# 13_Clocks_1.net
KiCad netlist of a schematic drawn in Altium Designer
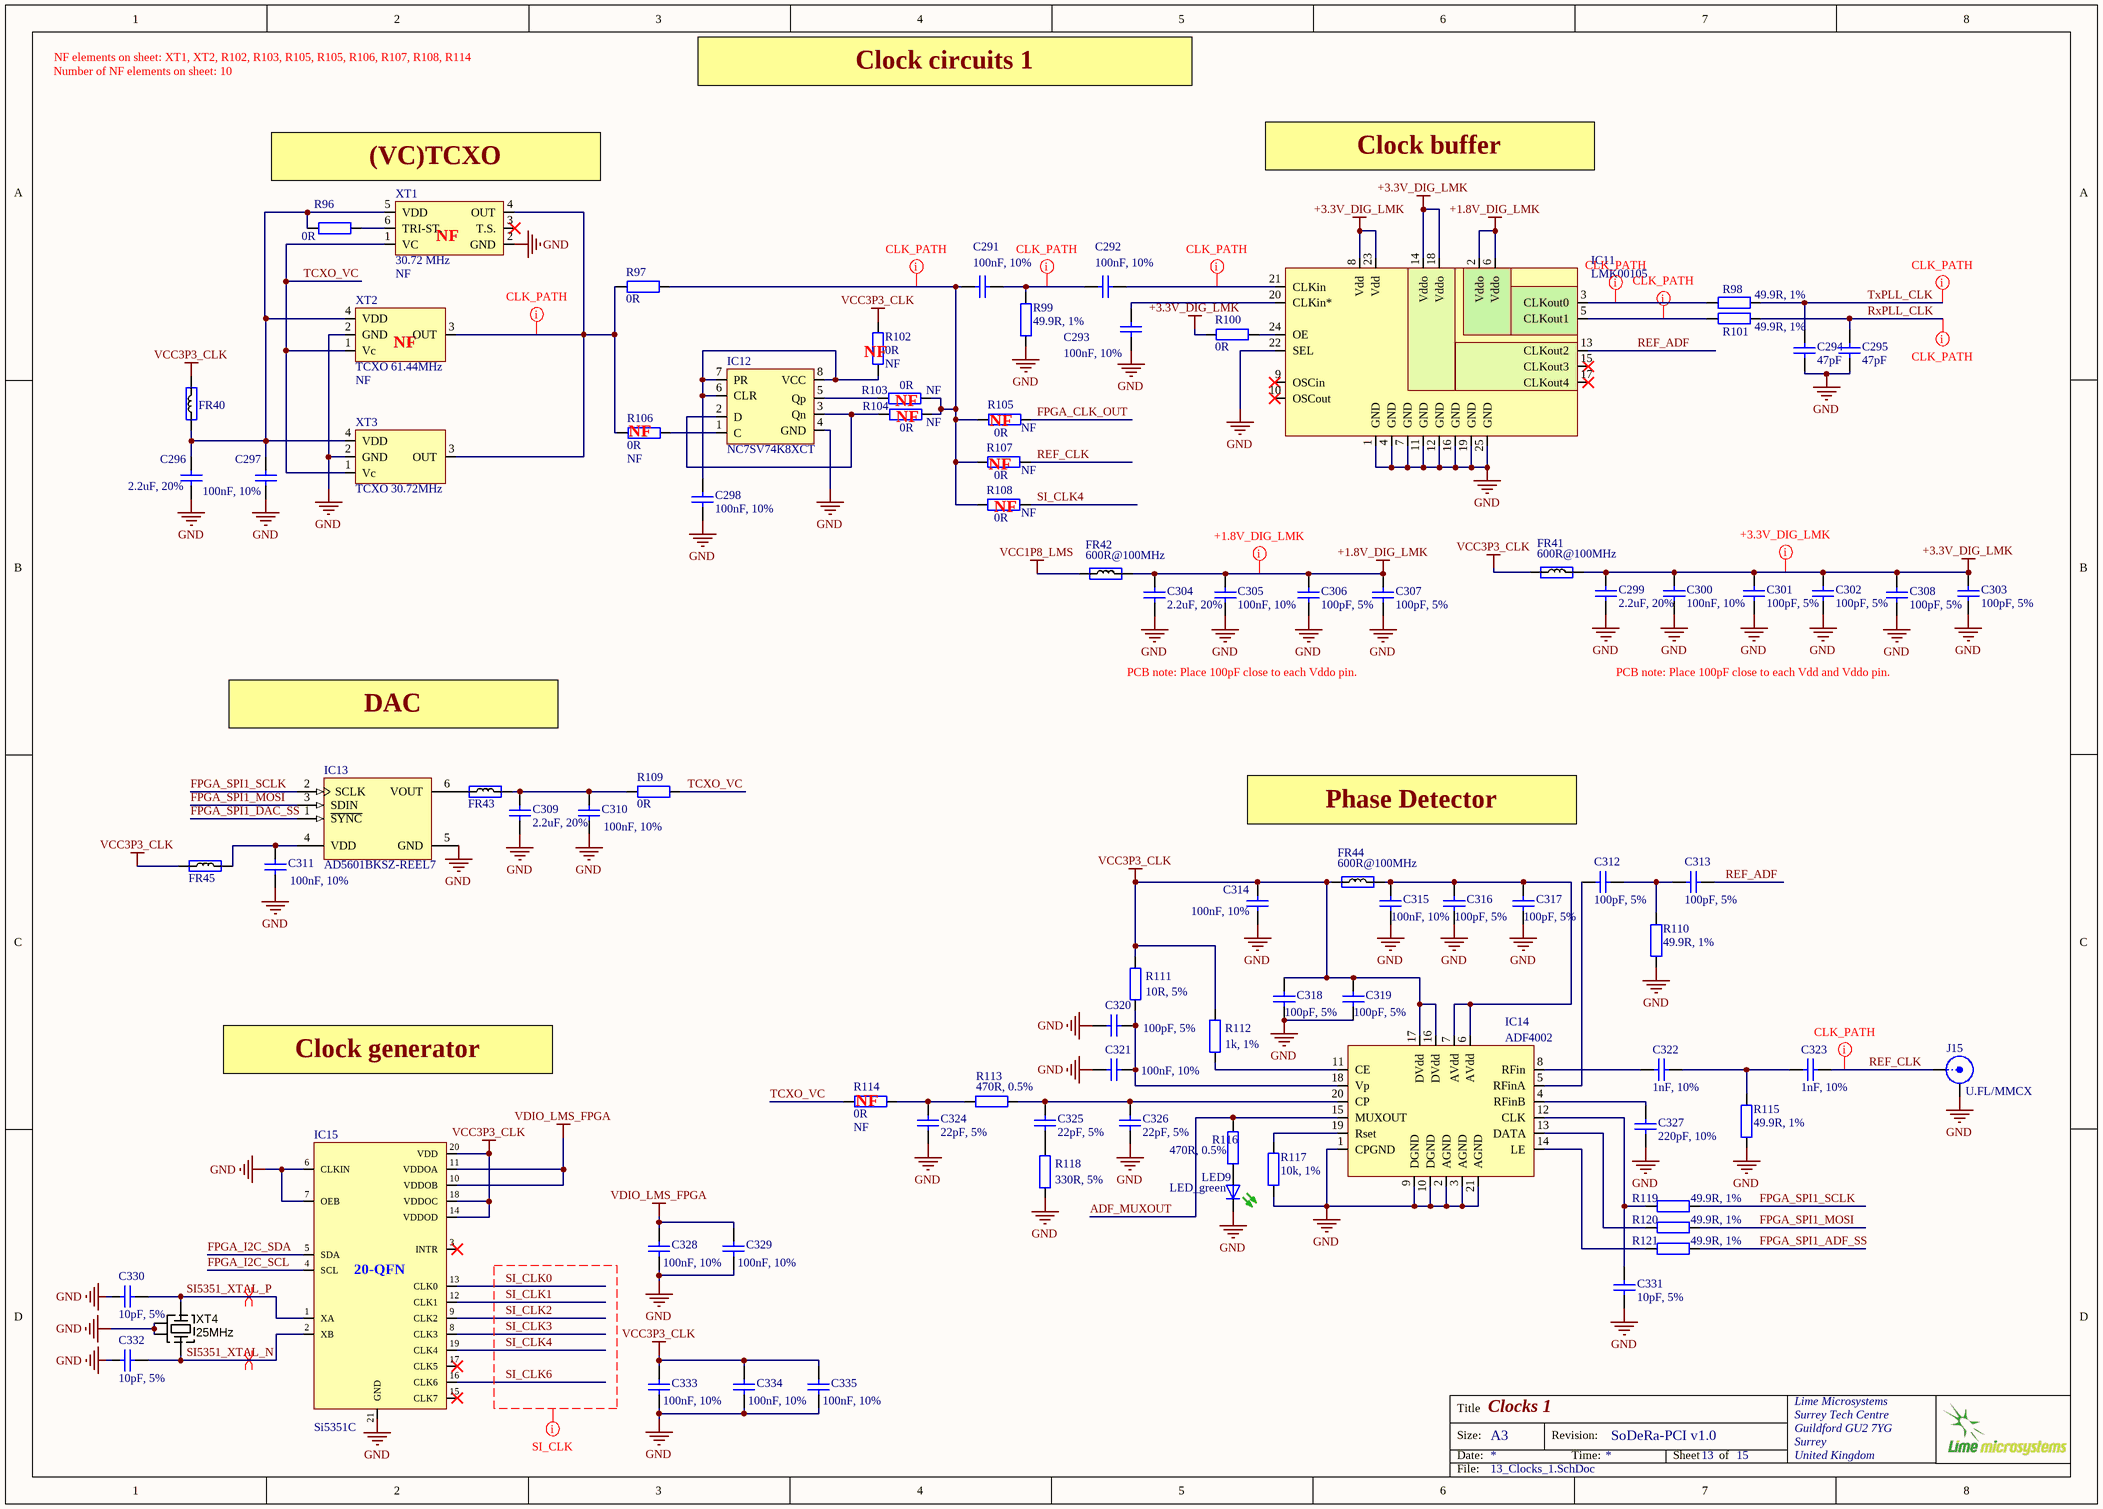
[diagram p0: 13_Clocks_1.SchDoc]

(export (version "E")
  (design (tool "Eeschema 10.0.6"))
  (components
    (comp (ref "C291")
      (value "100nF, 10%")
      (footprint "LimeMicroAltiumLib_pcbLib:CAP0402")
      (fields
        (field (name "MANUFACTURER") "Murata Electronics")
        (field (name "TOLERANCE") "10 %")
        (field (name "MANUFACTURER PART NUMBER") "GRM155R71C104KA88D")
      )
      (libsource (lib "LimeMicroAltiumLib_schLib") (part "Cap_0402"))
    )
    (comp (ref "C292")
      (value "100nF, 10%")
      (footprint "LimeMicroAltiumLib_pcbLib:CAP0402")
      (fields
        (field (name "MANUFACTURER") "Murata Electronics")
        (field (name "TOLERANCE") "10 %")
        (field (name "MANUFACTURER PART NUMBER") "GRM155R71C104KA88D")
      )
      (libsource (lib "LimeMicroAltiumLib_schLib") (part "Cap_0402"))
    )
    (comp (ref "C293")
      (value "100nF, 10%")
      (footprint "LimeMicroAltiumLib_pcbLib:CAP0402")
      (fields
        (field (name "MANUFACTURER") "Murata Electronics")
        (field (name "TOLERANCE") "10 %")
        (field (name "MANUFACTURER PART NUMBER") "GRM155R71C104KA88D")
      )
      (libsource (lib "LimeMicroAltiumLib_schLib") (part "Cap_0402"))
    )
    (comp (ref "C294")
      (value "47pF")
      (footprint "LimeMicroAltiumLib_pcbLib:CAP0402")
      (fields (field (name "TOLERANCE") "±1%") (field (name "MANUFACTURER") "TDK Corporation"))
      (libsource (lib "LimeMicroAltiumLib_schLib") (part "Cap_0402"))
    )
    (comp (ref "C295")
      (value "47pF")
      (footprint "LimeMicroAltiumLib_pcbLib:CAP0402")
      (fields (field (name "TOLERANCE") "±1%") (field (name "MANUFACTURER") "TDK Corporation"))
      (libsource (lib "LimeMicroAltiumLib_schLib") (part "Cap_0402"))
    )
    (comp (ref "C296")
      (value "2.2uF, 20%")
      (footprint "LimeMicroAltiumLib_pcbLib:CAP0402")
      (fields (field (name "MANUFACTURER") "TDK Corporation") (field (name "TOLERANCE") "±20%"))
      (libsource (lib "LimeMicroAltiumLib_schLib") (part "Cap_0402"))
    )
    (comp (ref "C297")
      (value "100nF, 10%")
      (footprint "LimeMicroAltiumLib_pcbLib:CAP0402")
      (fields
        (field (name "MANUFACTURER") "Murata Electronics")
        (field (name "TOLERANCE") "10 %")
        (field (name "MANUFACTURER PART NUMBER") "GRM155R71C104KA88D")
      )
      (libsource (lib "LimeMicroAltiumLib_schLib") (part "Cap_0402"))
    )
    (comp (ref "C298")
      (value "100nF, 10%")
      (footprint "LimeMicroAltiumLib_pcbLib:CAP0402")
      (fields
        (field (name "MANUFACTURER") "Murata Electronics")
        (field (name "TOLERANCE") "10 %")
        (field (name "MANUFACTURER PART NUMBER") "GRM155R71C104KA88D")
      )
      (libsource (lib "LimeMicroAltiumLib_schLib") (part "Cap_0402"))
    )
    (comp (ref "C299")
      (value "2.2uF, 20%")
      (footprint "LimeMicroAltiumLib_pcbLib:CAP0402")
      (fields (field (name "MANUFACTURER") "TDK Corporation") (field (name "TOLERANCE") "±20%"))
      (libsource (lib "LimeMicroAltiumLib_schLib") (part "Cap_0402"))
    )
    (comp (ref "C300")
      (value "100nF, 10%")
      (footprint "LimeMicroAltiumLib_pcbLib:CAP0402")
      (fields
        (field (name "MANUFACTURER") "Murata Electronics")
        (field (name "TOLERANCE") "10 %")
        (field (name "MANUFACTURER PART NUMBER") "GRM155R71C104KA88D")
      )
      (libsource (lib "LimeMicroAltiumLib_schLib") (part "Cap_0402"))
    )
    (comp (ref "C301")
      (value "100pF, 5%")
      (footprint "LimeMicroAltiumLib_pcbLib:CAP0402")
      (fields (field (name "MANUFACTURER") "Yageo") (field (name "TOLERANCE") "±5%"))
      (libsource (lib "LimeMicroAltiumLib_schLib") (part "Cap_0402"))
    )
    (comp (ref "C302")
      (value "100pF, 5%")
      (footprint "LimeMicroAltiumLib_pcbLib:CAP0402")
      (fields (field (name "MANUFACTURER") "Yageo") (field (name "TOLERANCE") "±5%"))
      (libsource (lib "LimeMicroAltiumLib_schLib") (part "Cap_0402"))
    )
    (comp (ref "C303")
      (value "100pF, 5%")
      (footprint "LimeMicroAltiumLib_pcbLib:CAP0402")
      (fields (field (name "MANUFACTURER") "Yageo") (field (name "TOLERANCE") "±5%"))
      (libsource (lib "LimeMicroAltiumLib_schLib") (part "Cap_0402"))
    )
    (comp (ref "C304")
      (value "2.2uF, 20%")
      (footprint "LimeMicroAltiumLib_pcbLib:CAP0402")
      (fields (field (name "MANUFACTURER") "TDK Corporation") (field (name "TOLERANCE") "±20%"))
      (libsource (lib "LimeMicroAltiumLib_schLib") (part "Cap_0402"))
    )
    (comp (ref "C305")
      (value "100nF, 10%")
      (footprint "LimeMicroAltiumLib_pcbLib:CAP0402")
      (fields
        (field (name "MANUFACTURER") "Murata Electronics")
        (field (name "TOLERANCE") "10 %")
        (field (name "MANUFACTURER PART NUMBER") "GRM155R71C104KA88D")
      )
      (libsource (lib "LimeMicroAltiumLib_schLib") (part "Cap_0402"))
    )
    (comp (ref "C306")
      (value "100pF, 5%")
      (footprint "LimeMicroAltiumLib_pcbLib:CAP0402")
      (fields (field (name "MANUFACTURER") "Yageo") (field (name "TOLERANCE") "±5%"))
      (libsource (lib "LimeMicroAltiumLib_schLib") (part "Cap_0402"))
    )
    (comp (ref "C307")
      (value "100pF, 5%")
      (footprint "LimeMicroAltiumLib_pcbLib:CAP0402")
      (fields (field (name "MANUFACTURER") "Yageo") (field (name "TOLERANCE") "±5%"))
      (libsource (lib "LimeMicroAltiumLib_schLib") (part "Cap_0402"))
    )
    (comp (ref "C308")
      (value "100pF, 5%")
      (footprint "LimeMicroAltiumLib_pcbLib:CAP0402")
      (fields (field (name "MANUFACTURER") "Yageo") (field (name "TOLERANCE") "±5%"))
      (libsource (lib "LimeMicroAltiumLib_schLib") (part "Cap_0402"))
    )
    (comp (ref "C309")
      (value "2.2uF, 20%")
      (footprint "LimeMicroAltiumLib_pcbLib:CAP0402")
      (fields (field (name "MANUFACTURER") "TDK Corporation") (field (name "TOLERANCE") "±20%"))
      (libsource (lib "LimeMicroAltiumLib_schLib") (part "Cap_0402"))
    )
    (comp (ref "C310")
      (value "100nF, 10%")
      (footprint "LimeMicroAltiumLib_pcbLib:CAP0402")
      (fields
        (field (name "TOLERANCE") "10 %")
        (field (name "MANUFACTURER") "Murata")
        (field (name "MANUFACTURER PART NUMBER") "GRM155R71C104KA88D")
      )
      (libsource (lib "LimeFPGAboard_schLib") (part "Cap_0603"))
    )
    (comp (ref "C311")
      (value "100nF, 10%")
      (footprint "LimeMicroAltiumLib_pcbLib:CAP0402")
      (fields
        (field (name "TOLERANCE") "10 %")
        (field (name "MANUFACTURER") "Murata")
        (field (name "MANUFACTURER PART NUMBER") "GRM155R71C104KA88D")
      )
      (libsource (lib "LimeFPGAboard_schLib") (part "Cap_0603"))
    )
    (comp (ref "C312")
      (value "100pF, 5%")
      (footprint "LimeMicroAltiumLib_pcbLib:CAP0402")
      (fields (field (name "MANUFACTURER") "Yageo") (field (name "TOLERANCE") "±5%"))
      (libsource (lib "LimeMicroAltiumLib_schLib") (part "Cap_0402"))
    )
    (comp (ref "C313")
      (value "100pF, 5%")
      (footprint "LimeMicroAltiumLib_pcbLib:CAP0402")
      (fields (field (name "MANUFACTURER") "Yageo") (field (name "TOLERANCE") "±5%"))
      (libsource (lib "LimeMicroAltiumLib_schLib") (part "Cap_0402"))
    )
    (comp (ref "C314")
      (value "100nF, 10%")
      (footprint "LimeMicroAltiumLib_pcbLib:CAP0402")
      (fields
        (field (name "MANUFACTURER") "Murata Electronics")
        (field (name "TOLERANCE") "10 %")
        (field (name "MANUFACTURER PART NUMBER") "GRM155R71C104KA88D")
      )
      (libsource (lib "LimeMicroAltiumLib_schLib") (part "Cap_0402"))
    )
    (comp (ref "C315")
      (value "100nF, 10%")
      (footprint "LimeMicroAltiumLib_pcbLib:CAP0402")
      (fields
        (field (name "MANUFACTURER") "Murata Electronics")
        (field (name "TOLERANCE") "10 %")
        (field (name "MANUFACTURER PART NUMBER") "GRM155R71C104KA88D")
      )
      (libsource (lib "LimeMicroAltiumLib_schLib") (part "Cap_0402"))
    )
    (comp (ref "C316")
      (value "100pF, 5%")
      (footprint "LimeMicroAltiumLib_pcbLib:CAP0402")
      (fields (field (name "MANUFACTURER") "Yageo") (field (name "TOLERANCE") "±5%"))
      (libsource (lib "LimeMicroAltiumLib_schLib") (part "Cap_0402"))
    )
    (comp (ref "C317")
      (value "100pF, 5%")
      (footprint "LimeMicroAltiumLib_pcbLib:CAP0402")
      (fields (field (name "MANUFACTURER") "Yageo") (field (name "TOLERANCE") "±5%"))
      (libsource (lib "LimeMicroAltiumLib_schLib") (part "Cap_0402"))
    )
    (comp (ref "C318")
      (value "100pF, 5%")
      (footprint "LimeMicroAltiumLib_pcbLib:CAP0402")
      (fields (field (name "MANUFACTURER") "Yageo") (field (name "TOLERANCE") "±5%"))
      (libsource (lib "LimeMicroAltiumLib_schLib") (part "Cap_0402"))
    )
    (comp (ref "C319")
      (value "100pF, 5%")
      (footprint "LimeMicroAltiumLib_pcbLib:CAP0402")
      (fields (field (name "MANUFACTURER") "Yageo") (field (name "TOLERANCE") "±5%"))
      (libsource (lib "LimeMicroAltiumLib_schLib") (part "Cap_0402"))
    )
    (comp (ref "C320")
      (value "100pF, 5%")
      (footprint "LimeMicroAltiumLib_pcbLib:CAP0402")
      (fields (field (name "MANUFACTURER") "Yageo") (field (name "TOLERANCE") "±5%"))
      (libsource (lib "LimeMicroAltiumLib_schLib") (part "Cap_0402"))
    )
    (comp (ref "C321")
      (value "100nF, 10%")
      (footprint "LimeMicroAltiumLib_pcbLib:CAP0402")
      (fields
        (field (name "MANUFACTURER") "Murata Electronics")
        (field (name "TOLERANCE") "10 %")
        (field (name "MANUFACTURER PART NUMBER") "GRM155R71C104KA88D")
      )
      (libsource (lib "LimeMicroAltiumLib_schLib") (part "Cap_0402"))
    )
    (comp (ref "C322")
      (value "1nF, 10%")
      (footprint "LimeMicroAltiumLib_pcbLib:CAP0402")
      (fields (field (name "TOLERANCE") "10 %") (field (name "MANUFACTURER") "Murata Electronics"))
      (libsource (lib "LimeMicroAltiumLib_schLib") (part "Cap_0402"))
    )
    (comp (ref "C323")
      (value "1nF, 10%")
      (footprint "LimeMicroAltiumLib_pcbLib:CAP0402")
      (fields (field (name "TOLERANCE") "10 %") (field (name "MANUFACTURER") "Murata Electronics"))
      (libsource (lib "LimeMicroAltiumLib_schLib") (part "Cap_0402"))
    )
    (comp (ref "C324")
      (value "22pF, 5%")
      (footprint "LimeMicroAltiumLib_pcbLib:CAP0402")
      (fields (field (name "TOLERANCE") "±5%") (field (name "MANUFACTURER") "Yageo"))
      (libsource (lib "LimeMicroAltiumLib_schLib") (part "Cap_0402"))
    )
    (comp (ref "C325")
      (value "22pF, 5%")
      (footprint "LimeMicroAltiumLib_pcbLib:CAP0402")
      (fields (field (name "TOLERANCE") "±5%") (field (name "MANUFACTURER") "Yageo"))
      (libsource (lib "LimeMicroAltiumLib_schLib") (part "Cap_0402"))
    )
    (comp (ref "C326")
      (value "22pF, 5%")
      (footprint "LimeMicroAltiumLib_pcbLib:CAP0402")
      (fields (field (name "TOLERANCE") "±5%") (field (name "MANUFACTURER") "Yageo"))
      (libsource (lib "LimeMicroAltiumLib_schLib") (part "Cap_0402"))
    )
    (comp (ref "C327")
      (value "220pF, 10%")
      (footprint "LimeMicroAltiumLib_pcbLib:CAP0402")
      (fields (field (name "MANUFACTURER") "Yageo") (field (name "TOLERANCE") "±10%"))
      (libsource (lib "LimeMicroAltiumLib_schLib") (part "Cap_0402"))
    )
    (comp (ref "C328")
      (value "100nF, 10%")
      (footprint "LimeMicroAltiumLib_pcbLib:CAP0402")
      (fields
        (field (name "TOLERANCE") "10 %")
        (field (name "MANUFACTURER") "Murata")
        (field (name "MANUFACTURER PART NUMBER") "GRM155R71C104KA88D")
      )
      (libsource (lib "LimeFPGAboard_schLib") (part "Cap_0603"))
    )
    (comp (ref "C329")
      (value "100nF, 10%")
      (footprint "LimeMicroAltiumLib_pcbLib:CAP0402")
      (fields
        (field (name "TOLERANCE") "10 %")
        (field (name "MANUFACTURER") "Murata")
        (field (name "MANUFACTURER PART NUMBER") "GRM155R71C104KA88D")
      )
      (libsource (lib "LimeFPGAboard_schLib") (part "Cap_0603"))
    )
    (comp (ref "C330")
      (value "10pF, 5%")
      (footprint "LimeMicroAltiumLib_pcbLib:CAP0402")
      (fields (field (name "MANUFACTURER") "AVX"))
      (libsource (lib "LimeFPGAboard_schLib") (part "Cap_0402"))
    )
    (comp (ref "C331")
      (value "10pF, 5%")
      (footprint "LimeMicroAltiumLib_pcbLib:CAP0402")
      (fields (field (name "MANUFACTURER") "AVX"))
      (libsource (lib "LimeMicroAltiumLib_schLib") (part "Cap_0402"))
    )
    (comp (ref "C332")
      (value "10pF, 5%")
      (footprint "LimeMicroAltiumLib_pcbLib:CAP0402")
      (fields (field (name "MANUFACTURER") "AVX"))
      (libsource (lib "LimeFPGAboard_schLib") (part "Cap_0402"))
    )
    (comp (ref "C333")
      (value "100nF, 10%")
      (footprint "LimeMicroAltiumLib_pcbLib:CAP0402")
      (fields
        (field (name "TOLERANCE") "10 %")
        (field (name "MANUFACTURER") "Murata")
        (field (name "MANUFACTURER PART NUMBER") "GRM155R71C104KA88D")
      )
      (libsource (lib "LimeFPGAboard_schLib") (part "Cap_0603"))
    )
    (comp (ref "C334")
      (value "100nF, 10%")
      (footprint "LimeMicroAltiumLib_pcbLib:CAP0402")
      (fields
        (field (name "TOLERANCE") "10 %")
        (field (name "MANUFACTURER") "Murata")
        (field (name "MANUFACTURER PART NUMBER") "GRM155R71C104KA88D")
      )
      (libsource (lib "LimeFPGAboard_schLib") (part "Cap_0603"))
    )
    (comp (ref "C335")
      (value "100nF, 10%")
      (footprint "LimeMicroAltiumLib_pcbLib:CAP0402")
      (fields
        (field (name "TOLERANCE") "10 %")
        (field (name "MANUFACTURER") "Murata")
        (field (name "MANUFACTURER PART NUMBER") "GRM155R71C104KA88D")
      )
      (libsource (lib "LimeFPGAboard_schLib") (part "Cap_0603"))
    )
    (comp (ref "FR40")
      (value "Ferrite")
      (footprint "LimeMicroAltiumLib_pcbLib:RES0201")
      (fields (field (name "MANUFACTURER") "Taiyo Yuden"))
      (libsource (lib "LimeMicroAltiumLib_schLib") (part "Ferrite"))
    )
    (comp (ref "FR41")
      (value "600R@100MHz")
      (footprint "LimeMicroAltiumLib_pcbLib:RES0805")
      (fields (field (name "MANUFACTURER") "TDK Corporation"))
      (libsource (lib "LimeMicroAltiumLib_schLib") (part "Ferrite"))
    )
    (comp (ref "FR42")
      (value "600R@100MHz")
      (footprint "LimeMicroAltiumLib_pcbLib:RES0805")
      (fields (field (name "MANUFACTURER") "TDK Corporation"))
      (libsource (lib "LimeMicroAltiumLib_schLib") (part "Ferrite"))
    )
    (comp (ref "FR43")
      (value "Ferrite")
      (footprint "LimeMicroAltiumLib_pcbLib:RES0201")
      (fields (field (name "MANUFACTURER") "Taiyo Yuden"))
      (libsource (lib "LimeMicroAltiumLib_schLib") (part "Ferrite"))
    )
    (comp (ref "FR44")
      (value "600R@100MHz")
      (footprint "LimeMicroAltiumLib_pcbLib:RES0805")
      (fields (field (name "MANUFACTURER") "TDK Corporation"))
      (libsource (lib "LimeMicroAltiumLib_schLib") (part "Ferrite"))
    )
    (comp (ref "FR45")
      (value "Ferrite")
      (footprint "LimeMicroAltiumLib_pcbLib:RES0201")
      (fields (field (name "MANUFACTURER") "Taiyo Yuden"))
      (libsource (lib "LimeMicroAltiumLib_schLib") (part "Ferrite"))
    )
    (comp (ref "IC11")
      (value "LMK00105")
      (footprint "LMK00105SQ")
      (fields (field (name "MANUFACTURER") "Texas Instruments"))
      (libsource (lib "LimeMicroAltiumLib_schLib") (part "LMK00105"))
    )
    (comp (ref "IC12")
      (value "NC7SV74K8XCT")
      (footprint "LimeMicroAltiumLib_pcbLib:NC7SV74K8XCT")
      (fields (field (name "MANUFACTURER") "Fairchild Semiconductor"))
      (libsource (lib "LimeMicroAltiumLib_schLib") (part "NC7SV74K8XCT"))
    )
    (comp (ref "IC13")
      (value "AD5601BKSZ-REEL7")
      (footprint "LimeMicroAltiumLib_pcbLib:AD5601_SOT23-6")
      (fields (field (name "GENERIC PART NUMBER") "AD5601") (field (name "MANUFACTURER") "Analog Devices"))
      (libsource (lib "LimeMicroAltiumLib_schLib") (part "AD5601BKSZ-REEL7"))
    )
    (comp (ref "IC14")
      (value "ADF4002")
      (footprint "LimeMicroAltiumLib_pcbLib:ADF4002")
      (fields (field (name "MANUFACTURER") "Analog Devices Inc"))
      (libsource (lib "LimeMicroAltiumLib_schLib") (part "ADF4002"))
    )
    (comp (ref "IC15")
      (value "Si5351C")
      (footprint "LimeMicroAltiumLib_pcbLib:Si5351C_20QFN")
      (fields (field (name "MANUFACTURER") "Silicon Labs"))
      (libsource (lib "LimeFPGAboard_schLib") (part "Si5351C"))
    )
    (comp (ref "J15")
      (value "U.FL/MMCX")
      (footprint "LimeMicroAltiumLib_pcbLib:MMCX_UFL_conn_u")
      (fields (field (name "MANUFACTURER") "Molex, LLC"))
      (libsource (lib "LimeMicroAltiumLib_schLib") (part "RF_IF_connector"))
    )
    (comp (ref "LED9")
      (value "LED_green")
      (footprint "LimeMicroAltiumLib_pcbLib:LED-0603-GREEN")
      (libsource (lib "LimeFPGAboard_schLib") (part "LED_green"))
    )
    (comp (ref "R96")
      (value "0R")
      (footprint "LimeMicroAltiumLib_pcbLib:RES0402")
      (fields (field (name "MANUFACTURER") "Yageo") (field (name "TOLERANCE") "Jumper"))
      (libsource (lib "LimeMicroAltiumLib_schLib") (part "Res_0402"))
    )
    (comp (ref "R97")
      (value "0R")
      (footprint "LimeMicroAltiumLib_pcbLib:RES0402")
      (fields (field (name "MANUFACTURER") "Yageo") (field (name "TOLERANCE") "Jumper"))
      (libsource (lib "LimeMicroAltiumLib_schLib") (part "Res_0402"))
    )
    (comp (ref "R98")
      (value "49.9R, 1%")
      (footprint "LimeMicroAltiumLib_pcbLib:RES0402")
      (fields
        (field (name "TOLERANCE") "±1%")
        (field (name "MANUFACTURER") "Samsung Electro-Mechanics America, Inc.")
        (field (name "MANUFACTURER PART NUMBER") "RC1005F49R9CS")
      )
      (libsource (lib "LimeMicroAltiumLib_schLib") (part "Res_0402"))
    )
    (comp (ref "R99")
      (value "49.9R, 1%")
      (footprint "LimeMicroAltiumLib_pcbLib:RES0402")
      (fields
        (field (name "TOLERANCE") "±1%")
        (field (name "MANUFACTURER") "Samsung Electro-Mechanics America, Inc.")
        (field (name "MANUFACTURER PART NUMBER") "RC1005F49R9CS")
      )
      (libsource (lib "LimeMicroAltiumLib_schLib") (part "Res_0402"))
    )
    (comp (ref "R100")
      (value "0R")
      (footprint "LimeMicroAltiumLib_pcbLib:RES0402")
      (fields (field (name "MANUFACTURER") "Yageo") (field (name "TOLERANCE") "Jumper"))
      (libsource (lib "LimeMicroAltiumLib_schLib") (part "Res_0402"))
    )
    (comp (ref "R101")
      (value "49.9R, 1%")
      (footprint "LimeMicroAltiumLib_pcbLib:RES0402")
      (fields
        (field (name "TOLERANCE") "±1%")
        (field (name "MANUFACTURER") "Samsung Electro-Mechanics America, Inc.")
        (field (name "MANUFACTURER PART NUMBER") "RC1005F49R9CS")
      )
      (libsource (lib "LimeMicroAltiumLib_schLib") (part "Res_0402"))
    )
    (comp (ref "R102")
      (value "0R")
      (footprint "LimeMicroAltiumLib_pcbLib:RES0402")
      (fields
        (field (name "ASSEMBLY INFO") "NF")
        (field (name "MANUFACTURER") "Yageo")
        (field (name "TOLERANCE") "Jumper")
      )
      (libsource (lib "LimeMicroAltiumLib_schLib") (part "Res_0402"))
    )
    (comp (ref "R103")
      (value "0R")
      (footprint "LimeMicroAltiumLib_pcbLib:RES0402")
      (fields
        (field (name "ASSEMBLY INFO") "NF")
        (field (name "MANUFACTURER") "Yageo")
        (field (name "TOLERANCE") "Jumper")
      )
      (libsource (lib "LimeMicroAltiumLib_schLib") (part "Res_0402"))
    )
    (comp (ref "R104")
      (value "0R")
      (footprint "LimeMicroAltiumLib_pcbLib:RES0402")
      (fields
        (field (name "ASSEMBLY INFO") "NF")
        (field (name "MANUFACTURER") "Yageo")
        (field (name "TOLERANCE") "Jumper")
      )
      (libsource (lib "LimeMicroAltiumLib_schLib") (part "Res_0402"))
    )
    (comp (ref "R105")
      (value "0R")
      (footprint "LimeMicroAltiumLib_pcbLib:RES0402")
      (fields
        (field (name "ASSEMBLY INFO") "NF")
        (field (name "MANUFACTURER") "Yageo")
        (field (name "TOLERANCE") "Jumper")
      )
      (libsource (lib "LimeMicroAltiumLib_schLib") (part "Res_0402"))
    )
    (comp (ref "R106")
      (value "0R")
      (footprint "LimeMicroAltiumLib_pcbLib:RES0402")
      (fields
        (field (name "ASSEMBLY INFO") "NF")
        (field (name "MANUFACTURER") "Yageo")
        (field (name "TOLERANCE") "Jumper")
      )
      (libsource (lib "LimeMicroAltiumLib_schLib") (part "Res_0402"))
    )
    (comp (ref "R107")
      (value "0R")
      (footprint "LimeMicroAltiumLib_pcbLib:RES0402")
      (fields
        (field (name "ASSEMBLY INFO") "NF")
        (field (name "MANUFACTURER") "Yageo")
        (field (name "TOLERANCE") "Jumper")
      )
      (libsource (lib "LimeMicroAltiumLib_schLib") (part "Res_0402"))
    )
    (comp (ref "R108")
      (value "0R")
      (footprint "LimeMicroAltiumLib_pcbLib:RES0402")
      (fields
        (field (name "ASSEMBLY INFO") "NF")
        (field (name "MANUFACTURER") "Yageo")
        (field (name "TOLERANCE") "Jumper")
      )
      (libsource (lib "LimeMicroAltiumLib_schLib") (part "Res_0402"))
    )
    (comp (ref "R109")
      (value "0R")
      (footprint "LimeMicroAltiumLib_pcbLib:RES0402")
      (fields (field (name "MANUFACTURER") "Yageo") (field (name "TOLERANCE") "Jumper"))
      (libsource (lib "LimeMicroAltiumLib_schLib") (part "Res_0402"))
    )
    (comp (ref "R110")
      (value "49.9R, 1%")
      (footprint "LimeMicroAltiumLib_pcbLib:RES0402")
      (fields
        (field (name "TOLERANCE") "±1%")
        (field (name "MANUFACTURER") "Samsung Electro-Mechanics America, Inc.")
        (field (name "MANUFACTURER PART NUMBER") "RC1005F49R9CS")
      )
      (libsource (lib "LimeMicroAltiumLib_schLib") (part "Res_0402"))
    )
    (comp (ref "R111")
      (value "10R, 5%")
      (footprint "LimeMicroAltiumLib_pcbLib:RES0402")
      (fields (field (name "TOLERANCE") "±5%") (field (name "MANUFACTURER") "Yageo"))
      (libsource (lib "LimeMicroAltiumLib_schLib") (part "Res_0402"))
    )
    (comp (ref "R112")
      (value "1k, 1%")
      (footprint "LimeMicroAltiumLib_pcbLib:RES0402")
      (fields (field (name "MANUFACTURER") "Stackpole Electronics Inc") (field (name "TOLERANCE") "±1%"))
      (libsource (lib "LimeMicroAltiumLib_schLib") (part "Res_0402"))
    )
    (comp (ref "R113")
      (value "470R, 0.5%")
      (footprint "LimeMicroAltiumLib_pcbLib:RES0402")
      (fields
        (field (name "TOLERANCE") "±0.5%")
        (field (name "MANUFACTURER") "Panasonic Electronic Components")
      )
      (libsource (lib "LimeMicroAltiumLib_schLib") (part "Res_0402"))
    )
    (comp (ref "R114")
      (value "0R")
      (footprint "LimeMicroAltiumLib_pcbLib:RES0402")
      (fields
        (field (name "ASSEMBLY INFO") "NF")
        (field (name "MANUFACTURER") "Yageo")
        (field (name "TOLERANCE") "Jumper")
      )
      (libsource (lib "LimeMicroAltiumLib_schLib") (part "Res_0402"))
    )
    (comp (ref "R115")
      (value "49.9R, 1%")
      (footprint "LimeMicroAltiumLib_pcbLib:RES0402")
      (fields
        (field (name "TOLERANCE") "±1%")
        (field (name "MANUFACTURER") "Samsung Electro-Mechanics America, Inc.")
        (field (name "MANUFACTURER PART NUMBER") "RC1005F49R9CS")
      )
      (libsource (lib "LimeMicroAltiumLib_schLib") (part "Res_0402"))
    )
    (comp (ref "R116")
      (value "470R, 0.5%")
      (footprint "LimeMicroAltiumLib_pcbLib:RES0402")
      (fields (field (name "TOLERANCE") "±0.5%"))
      (libsource (lib "LimeFPGAboard_schLib") (part "Res_0402"))
    )
    (comp (ref "R117")
      (value "10k, 1%")
      (footprint "LimeMicroAltiumLib_pcbLib:RES0402")
      (fields (field (name "MANUFACTURER") "Yageo") (field (name "TOLERANCE") "±1%"))
      (libsource (lib "LimeMicroAltiumLib_schLib") (part "Res_0402"))
    )
    (comp (ref "R118")
      (value "330R, 5%")
      (footprint "LimeMicroAltiumLib_pcbLib:RES0402")
      (fields (field (name "MANUFACTURER") "Yageo") (field (name "TOLERANCE") "±5%"))
      (libsource (lib "LimeMicroAltiumLib_schLib") (part "Res_0402"))
    )
    (comp (ref "R119")
      (value "49.9R, 1%")
      (footprint "LimeMicroAltiumLib_pcbLib:RES0402")
      (fields
        (field (name "TOLERANCE") "±1%")
        (field (name "MANUFACTURER") "Samsung Electro-Mechanics America, Inc.")
        (field (name "MANUFACTURER PART NUMBER") "RC1005F49R9CS")
      )
      (libsource (lib "LimeMicroAltiumLib_schLib") (part "Res_0402"))
    )
    (comp (ref "R120")
      (value "49.9R, 1%")
      (footprint "LimeMicroAltiumLib_pcbLib:RES0402")
      (fields
        (field (name "TOLERANCE") "±1%")
        (field (name "MANUFACTURER") "Samsung Electro-Mechanics America, Inc.")
        (field (name "MANUFACTURER PART NUMBER") "RC1005F49R9CS")
      )
      (libsource (lib "LimeMicroAltiumLib_schLib") (part "Res_0402"))
    )
    (comp (ref "R121")
      (value "49.9R, 1%")
      (footprint "LimeMicroAltiumLib_pcbLib:RES0402")
      (fields
        (field (name "TOLERANCE") "±1%")
        (field (name "MANUFACTURER") "Samsung Electro-Mechanics America, Inc.")
        (field (name "MANUFACTURER PART NUMBER") "RC1005F49R9CS")
      )
      (libsource (lib "LimeMicroAltiumLib_schLib") (part "Res_0402"))
    )
    (comp (ref "XT1")
      (value "30.72 MHz")
      (footprint "LimeMicroAltiumLib_pcbLib:RAKON_RPT7050A")
      (fields (field (name "ASSEMBLY INFO") "NF"))
      (libsource (lib "LimeMicroAltiumLib_schLib") (part "RPT7050A"))
    )
    (comp (ref "XT2")
      (value "TCXO 61.44MHz")
      (footprint "LimeMicroAltiumLib_pcbLib:RAKON_TXCO_61MHz_v2")
      (fields (field (name "ASSEMBLY INFO") "NF"))
      (libsource (lib "LimeMicroAltiumLib_schLib") (part "TXCO"))
    )
    (comp (ref "XT3")
      (value "TCXO 30.72MHz")
      (footprint "LimeMicroAltiumLib_pcbLib:RAKON_TXCO")
      (libsource (lib "LimeMicroAltiumLib_schLib") (part "TXCO"))
    )
    (comp (ref "XT4")
      (value "25MHz")
      (footprint "LimeMicroAltiumLib_pcbLib:CRYSTAL_4-LCC")
      (description "Oscillator Crystal 25 MHz")
      (fields (field (name "MANUFACTURER") "ABRACON"))
      (libsource (lib "LimeFPGAboard_schLib") (part "CRYSTAL_19M2"))
    )
  )
  (nets
    (net (code "1") (name "+1.8V_DIG_LMK") (class "Default")
      (node (ref "C304") (pin "2") (pinfunction "2_2") (pintype "passive"))
      (node (ref "C305") (pin "2") (pinfunction "2_2") (pintype "passive"))
      (node (ref "C306") (pin "2") (pinfunction "2_2") (pintype "passive"))
      (node (ref "C307") (pin "2") (pinfunction "2_2") (pintype "passive"))
      (node (ref "FR42") (pin "2") (pinfunction "2_2") (pintype "passive"))
      (node (ref "IC11") (pin "2") (pinfunction "Vddo_2") (pintype "passive"))
      (node (ref "IC11") (pin "6") (pinfunction "Vddo_6") (pintype "passive"))
    )
    (net (code "2") (name "+3.3V_DIG_LMK") (class "Default")
      (node (ref "C299") (pin "2") (pinfunction "2_2") (pintype "passive"))
      (node (ref "C300") (pin "2") (pinfunction "2_2") (pintype "passive"))
      (node (ref "C301") (pin "2") (pinfunction "2_2") (pintype "passive"))
      (node (ref "C302") (pin "2") (pinfunction "2_2") (pintype "passive"))
      (node (ref "C303") (pin "2") (pinfunction "2_2") (pintype "passive"))
      (node (ref "C308") (pin "2") (pinfunction "2_2") (pintype "passive"))
      (node (ref "FR41") (pin "2") (pinfunction "2_2") (pintype "passive"))
      (node (ref "IC11") (pin "14") (pinfunction "Vddo_14") (pintype "passive"))
      (node (ref "IC11") (pin "18") (pinfunction "Vddo_18") (pintype "passive"))
      (node (ref "IC11") (pin "23") (pinfunction "Vdd_23") (pintype "passive"))
      (node (ref "IC11") (pin "8") (pinfunction "Vdd_8") (pintype "passive"))
      (node (ref "R100") (pin "1") (pinfunction "1_1") (pintype "passive"))
    )
    (net (code "3") (name "/ADF_MUXOUT") (class "Default")
      (node (ref "IC14") (pin "15") (pinfunction "MUXOUT_15") (pintype "passive"))
      (node (ref "R116") (pin "2") (pinfunction "2_2") (pintype "passive"))
    )
    (net (code "4") (name "/FPGA_CLK_OUT") (class "Default")
      (node (ref "R105") (pin "1") (pinfunction "1_1") (pintype "passive"))
    )
    (net (code "5") (name "/FPGA_I2C_SCL") (class "Default")
      (node (ref "IC15") (pin "4") (pinfunction "SCL_4") (pintype "passive"))
    )
    (net (code "6") (name "/FPGA_I2C_SDA") (class "Default")
      (node (ref "IC15") (pin "5") (pinfunction "SDA_5") (pintype "passive"))
    )
    (net (code "7") (name "/FPGA_SPI1_ADF_SS") (class "Default")
      (node (ref "R121") (pin "1") (pinfunction "1_1") (pintype "passive"))
    )
    (net (code "8") (name "/FPGA_SPI1_DAC_SS") (class "Default")
      (node (ref "IC13") (pin "1") (pinfunction "~{SYNC}_1") (pintype "input"))
    )
    (net (code "9") (name "/FPGA_SPI1_MOSI") (class "Default")
      (node (ref "IC13") (pin "3") (pinfunction "SDIN_3") (pintype "input"))
      (node (ref "R120") (pin "1") (pinfunction "1_1") (pintype "passive"))
    )
    (net (code "10") (name "/FPGA_SPI1_SCLK") (class "Default")
      (node (ref "IC13") (pin "2") (pinfunction "SCLK_2") (pintype "input"))
      (node (ref "R119") (pin "1") (pinfunction "1_1") (pintype "passive"))
    )
    (net (code "11") (name "/REF_ADF") (class "Default")
      (node (ref "C313") (pin "2") (pinfunction "2_2") (pintype "passive"))
      (node (ref "IC11") (pin "13") (pinfunction "CLKout2_13") (pintype "passive"))
    )
    (net (code "12") (name "/REF_CLK") (class "Default")
      (node (ref "C323") (pin "1") (pinfunction "1_1") (pintype "passive"))
      (node (ref "J15") (pin "1") (pinfunction "X_1") (pintype "passive"))
      (node (ref "R107") (pin "2") (pinfunction "2_2") (pintype "passive"))
    )
    (net (code "13") (name "/RxPLL_CLK") (class "Default")
      (node (ref "C295") (pin "2") (pinfunction "2_2") (pintype "passive"))
      (node (ref "R101") (pin "1") (pinfunction "1_1") (pintype "passive"))
    )
    (net (code "14") (name "/SI5351_XTAL_N") (class "Default")
      (node (ref "C332") (pin "2") (pinfunction "2_2") (pintype "passive"))
      (node (ref "IC15") (pin "2") (pinfunction "XB_2") (pintype "passive"))
      (node (ref "XT4") (pin "3") (pinfunction "X_3") (pintype "passive"))
    )
    (net (code "15") (name "/SI5351_XTAL_P") (class "Default")
      (node (ref "C330") (pin "2") (pinfunction "2_2") (pintype "passive"))
      (node (ref "IC15") (pin "1") (pinfunction "XA_1") (pintype "passive"))
      (node (ref "XT4") (pin "1") (pinfunction "X_1") (pintype "passive"))
    )
    (net (code "16") (name "/SI_CLK0") (class "Default")
      (node (ref "IC15") (pin "13") (pinfunction "CLK0_13") (pintype "passive"))
    )
    (net (code "17") (name "/SI_CLK1") (class "Default")
      (node (ref "IC15") (pin "12") (pinfunction "CLK1_12") (pintype "passive"))
    )
    (net (code "18") (name "/SI_CLK2") (class "Default")
      (node (ref "IC15") (pin "9") (pinfunction "CLK2_9") (pintype "passive"))
    )
    (net (code "19") (name "/SI_CLK3") (class "Default")
      (node (ref "IC15") (pin "8") (pinfunction "CLK3_8") (pintype "passive"))
    )
    (net (code "20") (name "/SI_CLK4") (class "Default")
      (node (ref "IC15") (pin "19") (pinfunction "CLK4_19") (pintype "passive"))
      (node (ref "R108") (pin "2") (pinfunction "2_2") (pintype "passive"))
    )
    (net (code "21") (name "/SI_CLK6") (class "Default")
      (node (ref "IC15") (pin "16") (pinfunction "CLK6_16") (pintype "passive"))
    )
    (net (code "22") (name "/TCXO_VC") (class "Default")
      (node (ref "R109") (pin "1") (pinfunction "1_1") (pintype "passive"))
      (node (ref "R114") (pin "2") (pinfunction "2_2") (pintype "passive"))
      (node (ref "XT1") (pin "1") (pinfunction "VC_1") (pintype "passive"))
      (node (ref "XT2") (pin "1") (pinfunction "Vc_1") (pintype "passive"))
      (node (ref "XT3") (pin "1") (pinfunction "Vc_1") (pintype "passive"))
    )
    (net (code "23") (name "/TxPLL_CLK") (class "Default")
      (node (ref "C294") (pin "2") (pinfunction "2_2") (pintype "passive"))
      (node (ref "R98") (pin "1") (pinfunction "1_1") (pintype "passive"))
    )
    (net (code "24") (name "GND") (class "Default")
      (node (ref "C293") (pin "1") (pinfunction "1_1") (pintype "passive"))
      (node (ref "C294") (pin "1") (pinfunction "1_1") (pintype "passive"))
      (node (ref "C295") (pin "1") (pinfunction "1_1") (pintype "passive"))
      (node (ref "C296") (pin "1") (pinfunction "1_1") (pintype "passive"))
      (node (ref "C297") (pin "1") (pinfunction "1_1") (pintype "passive"))
      (node (ref "C298") (pin "1") (pinfunction "1_1") (pintype "passive"))
      (node (ref "C299") (pin "1") (pinfunction "1_1") (pintype "passive"))
      (node (ref "C300") (pin "1") (pinfunction "1_1") (pintype "passive"))
      (node (ref "C301") (pin "1") (pinfunction "1_1") (pintype "passive"))
      (node (ref "C302") (pin "1") (pinfunction "1_1") (pintype "passive"))
      (node (ref "C303") (pin "1") (pinfunction "1_1") (pintype "passive"))
      (node (ref "C304") (pin "1") (pinfunction "1_1") (pintype "passive"))
      (node (ref "C305") (pin "1") (pinfunction "1_1") (pintype "passive"))
      (node (ref "C306") (pin "1") (pinfunction "1_1") (pintype "passive"))
      (node (ref "C307") (pin "1") (pinfunction "1_1") (pintype "passive"))
      (node (ref "C308") (pin "1") (pinfunction "1_1") (pintype "passive"))
      (node (ref "C309") (pin "1") (pinfunction "1_1") (pintype "passive"))
      (node (ref "C310") (pin "2") (pinfunction "2_2") (pintype "passive"))
      (node (ref "C311") (pin "2") (pinfunction "2_2") (pintype "passive"))
      (node (ref "C314") (pin "1") (pinfunction "1_1") (pintype "passive"))
      (node (ref "C315") (pin "1") (pinfunction "1_1") (pintype "passive"))
      (node (ref "C316") (pin "2") (pinfunction "2_2") (pintype "passive"))
      (node (ref "C317") (pin "2") (pinfunction "2_2") (pintype "passive"))
      (node (ref "C318") (pin "2") (pinfunction "2_2") (pintype "passive"))
      (node (ref "C319") (pin "2") (pinfunction "2_2") (pintype "passive"))
      (node (ref "C320") (pin "1") (pinfunction "1_1") (pintype "passive"))
      (node (ref "C321") (pin "2") (pinfunction "2_2") (pintype "passive"))
      (node (ref "C324") (pin "1") (pinfunction "1_1") (pintype "passive"))
      (node (ref "C326") (pin "1") (pinfunction "1_1") (pintype "passive"))
      (node (ref "C327") (pin "2") (pinfunction "2_2") (pintype "passive"))
      (node (ref "C328") (pin "2") (pinfunction "2_2") (pintype "passive"))
      (node (ref "C329") (pin "2") (pinfunction "2_2") (pintype "passive"))
      (node (ref "C330") (pin "1") (pinfunction "1_1") (pintype "passive"))
      (node (ref "C331") (pin "1") (pinfunction "1_1") (pintype "passive"))
      (node (ref "C332") (pin "1") (pinfunction "1_1") (pintype "passive"))
      (node (ref "C333") (pin "2") (pinfunction "2_2") (pintype "passive"))
      (node (ref "C334") (pin "2") (pinfunction "2_2") (pintype "passive"))
      (node (ref "C335") (pin "2") (pinfunction "2_2") (pintype "passive"))
      (node (ref "IC11") (pin "1") (pinfunction "GND_1") (pintype "passive"))
      (node (ref "IC11") (pin "11") (pinfunction "GND_11") (pintype "passive"))
      (node (ref "IC11") (pin "12") (pinfunction "GND_12") (pintype "passive"))
      (node (ref "IC11") (pin "16") (pinfunction "GND_16") (pintype "passive"))
      (node (ref "IC11") (pin "19") (pinfunction "GND_19") (pintype "passive"))
      (node (ref "IC11") (pin "22") (pinfunction "SEL_22") (pintype "passive"))
      (node (ref "IC11") (pin "25") (pinfunction "GND_25") (pintype "passive"))
      (node (ref "IC11") (pin "4") (pinfunction "GND_4") (pintype "passive"))
      (node (ref "IC11") (pin "7") (pinfunction "GND_7") (pintype "passive"))
      (node (ref "IC12") (pin "4") (pinfunction "GND_4") (pintype "passive"))
      (node (ref "IC13") (pin "5") (pinfunction "GND_5") (pintype "power_in"))
      (node (ref "IC14") (pin "1") (pinfunction "CPGND_1") (pintype "passive"))
      (node (ref "IC14") (pin "10") (pinfunction "DGND_10") (pintype "passive"))
      (node (ref "IC14") (pin "2") (pinfunction "AGND_2") (pintype "passive"))
      (node (ref "IC14") (pin "21") (pinfunction "AGND_21") (pintype "passive"))
      (node (ref "IC14") (pin "3") (pinfunction "AGND_3") (pintype "passive"))
      (node (ref "IC14") (pin "9") (pinfunction "DGND_9") (pintype "passive"))
      (node (ref "IC15") (pin "21") (pinfunction "GND_21") (pintype "passive"))
      (node (ref "IC15") (pin "6") (pinfunction "CLKIN_6") (pintype "passive"))
      (node (ref "IC15") (pin "7") (pinfunction "OEB_7") (pintype "passive"))
      (node (ref "J15") (pin "2") (pinfunction "Y_2") (pintype "passive"))
      (node (ref "LED9") (pin "K") (pinfunction "C_K") (pintype "power_in"))
      (node (ref "R110") (pin "1") (pinfunction "1_1") (pintype "passive"))
      (node (ref "R115") (pin "1") (pinfunction "1_1") (pintype "passive"))
      (node (ref "R117") (pin "2") (pinfunction "2_2") (pintype "passive"))
      (node (ref "R118") (pin "1") (pinfunction "1_1") (pintype "passive"))
      (node (ref "R99") (pin "1") (pinfunction "1_1") (pintype "passive"))
      (node (ref "XT1") (pin "2") (pinfunction "GND_2") (pintype "passive"))
      (node (ref "XT2") (pin "2") (pinfunction "GND_2") (pintype "passive"))
      (node (ref "XT3") (pin "2") (pinfunction "GND_2") (pintype "passive"))
      (node (ref "XT4") (pin "2") (pinfunction "GND_2") (pintype "passive"))
      (node (ref "XT4") (pin "4") (pinfunction "GND_4") (pintype "passive"))
    )
    (net (code "25") (name "Net-(C291-Pad1)") (class "Default")
      (node (ref "C291") (pin "1") (pinfunction "1_1") (pintype "passive"))
      (node (ref "C292") (pin "2") (pinfunction "2_2") (pintype "passive"))
      (node (ref "R99") (pin "2") (pinfunction "2_2") (pintype "passive"))
    )
    (net (code "26") (name "Net-(C291-Pad2)") (class "Default")
      (node (ref "C291") (pin "2") (pinfunction "2_2") (pintype "passive"))
      (node (ref "R103") (pin "1") (pinfunction "1_1") (pintype "passive"))
      (node (ref "R104") (pin "1") (pinfunction "1_1") (pintype "passive"))
      (node (ref "R105") (pin "2") (pinfunction "2_2") (pintype "passive"))
      (node (ref "R107") (pin "1") (pinfunction "1_1") (pintype "passive"))
      (node (ref "R108") (pin "1") (pinfunction "1_1") (pintype "passive"))
      (node (ref "R97") (pin "1") (pinfunction "1_1") (pintype "passive"))
    )
    (net (code "27") (name "Net-(C309-Pad2)") (class "Default")
      (node (ref "C309") (pin "2") (pinfunction "2_2") (pintype "passive"))
      (node (ref "C310") (pin "1") (pinfunction "1_1") (pintype "passive"))
      (node (ref "FR43") (pin "2") (pinfunction "2_2") (pintype "passive"))
      (node (ref "R109") (pin "2") (pinfunction "2_2") (pintype "passive"))
    )
    (net (code "28") (name "Net-(C312-Pad2)") (class "Default")
      (node (ref "C312") (pin "2") (pinfunction "2_2") (pintype "passive"))
      (node (ref "C313") (pin "1") (pinfunction "1_1") (pintype "passive"))
      (node (ref "R110") (pin "2") (pinfunction "2_2") (pintype "passive"))
    )
    (net (code "29") (name "Net-(C315-Pad2)") (class "Default")
      (node (ref "C315") (pin "2") (pinfunction "2_2") (pintype "passive"))
      (node (ref "C316") (pin "1") (pinfunction "1_1") (pintype "passive"))
      (node (ref "C317") (pin "1") (pinfunction "1_1") (pintype "passive"))
      (node (ref "FR44") (pin "2") (pinfunction "2_2") (pintype "passive"))
      (node (ref "IC14") (pin "6") (pinfunction "AVdd_6") (pintype "passive"))
      (node (ref "IC14") (pin "7") (pinfunction "AVdd_7") (pintype "passive"))
    )
    (net (code "30") (name "Net-(C322-Pad1)") (class "Default")
      (node (ref "C322") (pin "1") (pinfunction "1_1") (pintype "passive"))
      (node (ref "C323") (pin "2") (pinfunction "2_2") (pintype "passive"))
      (node (ref "R115") (pin "2") (pinfunction "2_2") (pintype "passive"))
    )
    (net (code "31") (name "Net-(C324-Pad2)") (class "Default")
      (node (ref "C324") (pin "2") (pinfunction "2_2") (pintype "passive"))
      (node (ref "R113") (pin "2") (pinfunction "2_2") (pintype "passive"))
      (node (ref "R114") (pin "1") (pinfunction "1_1") (pintype "passive"))
    )
    (net (code "32") (name "Net-(C325-Pad1)") (class "Default")
      (node (ref "C325") (pin "1") (pinfunction "1_1") (pintype "passive"))
      (node (ref "R118") (pin "2") (pinfunction "2_2") (pintype "passive"))
    )
    (net (code "33") (name "Net-(IC11-CLKin)") (class "Default")
      (node (ref "C292") (pin "1") (pinfunction "1_1") (pintype "passive"))
      (node (ref "IC11") (pin "21") (pinfunction "CLKin_21") (pintype "passive"))
    )
    (net (code "34") (name "Net-(IC11-CLKin*)") (class "Default")
      (node (ref "C293") (pin "2") (pinfunction "2_2") (pintype "passive"))
      (node (ref "IC11") (pin "20") (pinfunction "CLKin*_20") (pintype "passive"))
    )
    (net (code "35") (name "Net-(IC11-CLKout0)") (class "Default")
      (node (ref "IC11") (pin "3") (pinfunction "CLKout0_3") (pintype "passive"))
      (node (ref "R98") (pin "2") (pinfunction "2_2") (pintype "passive"))
    )
    (net (code "36") (name "Net-(IC11-CLKout1)") (class "Default")
      (node (ref "IC11") (pin "5") (pinfunction "CLKout1_5") (pintype "passive"))
      (node (ref "R101") (pin "2") (pinfunction "2_2") (pintype "passive"))
    )
    (net (code "37") (name "Net-(IC11-OE)") (class "Default")
      (node (ref "IC11") (pin "24") (pinfunction "OE_24") (pintype "passive"))
      (node (ref "R100") (pin "2") (pinfunction "2_2") (pintype "passive"))
    )
    (net (code "38") (name "Net-(IC12-C)") (class "Default")
      (node (ref "IC12") (pin "1") (pinfunction "C_1") (pintype "passive"))
      (node (ref "R106") (pin "1") (pinfunction "1_1") (pintype "passive"))
    )
    (net (code "39") (name "Net-(IC12-CLR)") (class "Default")
      (node (ref "C298") (pin "2") (pinfunction "2_2") (pintype "passive"))
      (node (ref "IC12") (pin "6") (pinfunction "CLR_6") (pintype "passive"))
      (node (ref "IC12") (pin "7") (pinfunction "PR_7") (pintype "passive"))
      (node (ref "IC12") (pin "8") (pinfunction "VCC_8") (pintype "passive"))
      (node (ref "R102") (pin "2") (pinfunction "2_2") (pintype "passive"))
    )
    (net (code "40") (name "Net-(IC12-D)") (class "Default")
      (node (ref "IC12") (pin "2") (pinfunction "D_2") (pintype "passive"))
      (node (ref "IC12") (pin "3") (pinfunction "Qn_3") (pintype "passive"))
      (node (ref "R104") (pin "2") (pinfunction "2_2") (pintype "passive"))
    )
    (net (code "41") (name "Net-(IC12-Qp)") (class "Default")
      (node (ref "IC12") (pin "5") (pinfunction "Qp_5") (pintype "passive"))
      (node (ref "R103") (pin "2") (pinfunction "2_2") (pintype "passive"))
    )
    (net (code "42") (name "Net-(IC13-VDD)") (class "Default")
      (node (ref "C311") (pin "1") (pinfunction "1_1") (pintype "passive"))
      (node (ref "FR45") (pin "2") (pinfunction "2_2") (pintype "passive"))
      (node (ref "IC13") (pin "4") (pinfunction "VDD_4") (pintype "power_in"))
    )
    (net (code "43") (name "Net-(IC13-VOUT)") (class "Default")
      (node (ref "FR43") (pin "1") (pinfunction "1_1") (pintype "passive"))
      (node (ref "IC13") (pin "6") (pinfunction "VOUT_6") (pintype "tri_state"))
    )
    (net (code "44") (name "Net-(IC14-CE)") (class "Default")
      (node (ref "IC14") (pin "11") (pinfunction "CE_11") (pintype "passive"))
      (node (ref "R112") (pin "1") (pinfunction "1_1") (pintype "passive"))
    )
    (net (code "45") (name "Net-(IC14-CLK)") (class "Default")
      (node (ref "C331") (pin "2") (pinfunction "2_2") (pintype "passive"))
      (node (ref "IC14") (pin "12") (pinfunction "CLK_12") (pintype "passive"))
      (node (ref "R119") (pin "2") (pinfunction "2_2") (pintype "passive"))
    )
    (net (code "46") (name "Net-(IC14-CP)") (class "Default")
      (node (ref "C325") (pin "2") (pinfunction "2_2") (pintype "passive"))
      (node (ref "C326") (pin "2") (pinfunction "2_2") (pintype "passive"))
      (node (ref "IC14") (pin "20") (pinfunction "CP_20") (pintype "passive"))
      (node (ref "R113") (pin "1") (pinfunction "1_1") (pintype "passive"))
    )
    (net (code "47") (name "Net-(IC14-DATA)") (class "Default")
      (node (ref "IC14") (pin "13") (pinfunction "DATA_13") (pintype "passive"))
      (node (ref "R120") (pin "2") (pinfunction "2_2") (pintype "passive"))
    )
    (net (code "48") (name "Net-(IC14-LE)") (class "Default")
      (node (ref "IC14") (pin "14") (pinfunction "LE_14") (pintype "passive"))
      (node (ref "R121") (pin "2") (pinfunction "2_2") (pintype "passive"))
    )
    (net (code "49") (name "Net-(IC14-RFin)") (class "Default")
      (node (ref "C322") (pin "2") (pinfunction "2_2") (pintype "passive"))
      (node (ref "IC14") (pin "8") (pinfunction "RFin_8") (pintype "passive"))
    )
    (net (code "50") (name "Net-(IC14-RFinA)") (class "Default")
      (node (ref "C312") (pin "1") (pinfunction "1_1") (pintype "passive"))
      (node (ref "IC14") (pin "5") (pinfunction "RFinA_5") (pintype "passive"))
    )
    (net (code "51") (name "Net-(IC14-RFinB)") (class "Default")
      (node (ref "C327") (pin "1") (pinfunction "1_1") (pintype "passive"))
      (node (ref "IC14") (pin "4") (pinfunction "RFinB_4") (pintype "passive"))
    )
    (net (code "52") (name "Net-(IC14-Rset)") (class "Default")
      (node (ref "IC14") (pin "19") (pinfunction "Rset_19") (pintype "passive"))
      (node (ref "R117") (pin "1") (pinfunction "1_1") (pintype "passive"))
    )
    (net (code "53") (name "Net-(IC14-Vp)") (class "Default")
      (node (ref "C320") (pin "2") (pinfunction "2_2") (pintype "passive"))
      (node (ref "C321") (pin "1") (pinfunction "1_1") (pintype "passive"))
      (node (ref "IC14") (pin "18") (pinfunction "Vp_18") (pintype "passive"))
      (node (ref "R111") (pin "1") (pinfunction "1_1") (pintype "passive"))
    )
    (net (code "54") (name "Net-(LED9-PadA)") (class "Default")
      (node (ref "LED9") (pin "A") (pinfunction "A_A") (pintype "power_in"))
      (node (ref "R116") (pin "1") (pinfunction "1_1") (pintype "passive"))
    )
    (net (code "55") (name "Net-(XT1-OUT)") (class "Default")
      (node (ref "R106") (pin "2") (pinfunction "2_2") (pintype "passive"))
      (node (ref "R97") (pin "2") (pinfunction "2_2") (pintype "passive"))
      (node (ref "XT1") (pin "4") (pinfunction "OUT_4") (pintype "passive"))
      (node (ref "XT2") (pin "3") (pinfunction "OUT_3") (pintype "passive"))
      (node (ref "XT3") (pin "3") (pinfunction "OUT_3") (pintype "passive"))
    )
    (net (code "56") (name "Net-(XT1-TRI-ST.)") (class "Default")
      (node (ref "R96") (pin "1") (pinfunction "1_1") (pintype "passive"))
      (node (ref "XT1") (pin "6") (pinfunction "TRI-ST._6") (pintype "passive"))
    )
    (net (code "57") (name "Net-(XT1-VDD)") (class "Default")
      (node (ref "C296") (pin "2") (pinfunction "2_2") (pintype "passive"))
      (node (ref "C297") (pin "2") (pinfunction "2_2") (pintype "passive"))
      (node (ref "FR40") (pin "1") (pinfunction "1_1") (pintype "passive"))
      (node (ref "R96") (pin "2") (pinfunction "2_2") (pintype "passive"))
      (node (ref "XT1") (pin "5") (pinfunction "VDD_5") (pintype "passive"))
      (node (ref "XT2") (pin "4") (pinfunction "VDD_4") (pintype "passive"))
      (node (ref "XT3") (pin "4") (pinfunction "VDD_4") (pintype "passive"))
    )
    (net (code "58") (name "VCC1P8_LMS") (class "Default")
      (node (ref "FR42") (pin "1") (pinfunction "1_1") (pintype "passive"))
    )
    (net (code "59") (name "VCC3P3_CLK") (class "Default")
      (node (ref "C314") (pin "2") (pinfunction "2_2") (pintype "passive"))
      (node (ref "C318") (pin "1") (pinfunction "1_1") (pintype "passive"))
      (node (ref "C319") (pin "1") (pinfunction "1_1") (pintype "passive"))
      (node (ref "C333") (pin "1") (pinfunction "1_1") (pintype "passive"))
      (node (ref "C334") (pin "1") (pinfunction "1_1") (pintype "passive"))
      (node (ref "C335") (pin "1") (pinfunction "1_1") (pintype "passive"))
      (node (ref "FR40") (pin "2") (pinfunction "2_2") (pintype "passive"))
      (node (ref "FR41") (pin "1") (pinfunction "1_1") (pintype "passive"))
      (node (ref "FR44") (pin "1") (pinfunction "1_1") (pintype "passive"))
      (node (ref "FR45") (pin "1") (pinfunction "1_1") (pintype "passive"))
      (node (ref "IC14") (pin "16") (pinfunction "DVdd_16") (pintype "passive"))
      (node (ref "IC14") (pin "17") (pinfunction "DVdd_17") (pintype "passive"))
      (node (ref "IC15") (pin "14") (pinfunction "VDDOD_14") (pintype "passive"))
      (node (ref "IC15") (pin "18") (pinfunction "VDDOC_18") (pintype "passive"))
      (node (ref "IC15") (pin "20") (pinfunction "VDD_20") (pintype "passive"))
      (node (ref "R102") (pin "1") (pinfunction "1_1") (pintype "passive"))
      (node (ref "R111") (pin "2") (pinfunction "2_2") (pintype "passive"))
      (node (ref "R112") (pin "2") (pinfunction "2_2") (pintype "passive"))
    )
    (net (code "60") (name "VDIO_LMS_FPGA") (class "Default")
      (node (ref "C328") (pin "1") (pinfunction "1_1") (pintype "passive"))
      (node (ref "C329") (pin "1") (pinfunction "1_1") (pintype "passive"))
      (node (ref "IC15") (pin "10") (pinfunction "VDDOB_10") (pintype "passive"))
      (node (ref "IC15") (pin "11") (pinfunction "VDDOA_11") (pintype "passive"))
    )
    (net (code "61") (name "unconnected-(IC11-CLKout3-Pad15)") (class "Default")
      (node (ref "IC11") (pin "15") (pinfunction "CLKout3_15") (pintype "passive+no_connect"))
    )
    (net (code "62") (name "unconnected-(IC11-CLKout4-Pad17)") (class "Default")
      (node (ref "IC11") (pin "17") (pinfunction "CLKout4_17") (pintype "passive+no_connect"))
    )
    (net (code "63") (name "unconnected-(IC11-OSCin-Pad9)") (class "Default")
      (node (ref "IC11") (pin "9") (pinfunction "OSCin_9") (pintype "passive+no_connect"))
    )
    (net (code "64") (name "unconnected-(IC11-OSCout-Pad10)") (class "Default")
      (node (ref "IC11") (pin "10") (pinfunction "OSCout_10") (pintype "passive+no_connect"))
    )
    (net (code "65") (name "unconnected-(IC15-CLK5-Pad17)") (class "Default")
      (node (ref "IC15") (pin "17") (pinfunction "CLK5_17") (pintype "passive+no_connect"))
    )
    (net (code "66") (name "unconnected-(IC15-CLK7-Pad15)") (class "Default")
      (node (ref "IC15") (pin "15") (pinfunction "CLK7_15") (pintype "passive+no_connect"))
    )
    (net (code "67") (name "unconnected-(IC15-INTR-Pad3)") (class "Default")
      (node (ref "IC15") (pin "3") (pinfunction "INTR_3") (pintype "passive+no_connect"))
    )
    (net (code "68") (name "unconnected-(XT1-T.S.-Pad3)") (class "Default")
      (node (ref "XT1") (pin "3") (pinfunction "T.S._3") (pintype "passive+no_connect"))
    )
  )
)
